# MD2_SE_Colour_Fix_-_PAL_rev2.net
KiCad netlist of a schematic drawn in EAGLE
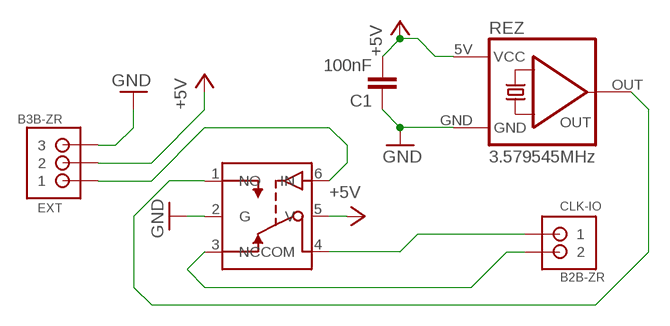
[diagram p0: schematic, sheet 1]

(export (version "E")
  (design (tool "Eeschema 10.0.6"))
  (components
    (comp (ref "C1")
      (value "100nF")
      (footprint "eagle-import:C0603K")
      (libsource (lib "eagle-import") (part "C-EUC0603K"))
    )
    (comp (ref "CLK-IO")
      (value "B2B-ZR")
      (footprint "eagle-import:B2B-ZR")
      (libsource (lib "eagle-import") (part "B2B-ZR"))
    )
    (comp (ref "EXT")
      (value "B3B-ZR")
      (footprint "eagle-import:B3B-ZR")
      (libsource (lib "eagle-import") (part "B3B-ZR"))
    )
    (comp (ref "REZ")
      (value "3.579545MHz")
      (footprint "eagle-import:DIL14S")
      (libsource (lib "eagle-import") (part "QG5860"))
    )
    (comp (ref "SWITCH")
      (value "TS5A3157EUT-T")
      (footprint "eagle-import:SOT23-6")
      (libsource (lib "eagle-import") (part "TS5A3157EUT-T"))
    )
  )
  (nets
    (net (code "1") (name "+5V") (class "Default")
      (node (ref "C1") (pin "2") (pinfunction "2_2") (pintype "passive"))
      (node (ref "EXT") (pin "2") (pinfunction "2_2") (pintype "bidirectional"))
      (node (ref "REZ") (pin "5V") (pinfunction "VCC_5V") (pintype "power_in"))
      (node (ref "SWITCH") (pin "5") (pinfunction "V_5") (pintype "power_in"))
    )
    (net (code "2") (name "GND") (class "Default")
      (node (ref "C1") (pin "1") (pinfunction "1_1") (pintype "passive"))
      (node (ref "EXT") (pin "3") (pinfunction "3_3") (pintype "bidirectional"))
      (node (ref "REZ") (pin "GND") (pinfunction "GND_GND") (pintype "power_in"))
      (node (ref "SWITCH") (pin "2") (pinfunction "G_2") (pintype "bidirectional"))
    )
    (net (code "3") (name "Net-(SWITCH-COM)") (class "Default")
      (node (ref "CLK-IO") (pin "1") (pinfunction "1_1") (pintype "bidirectional"))
      (node (ref "SWITCH") (pin "4") (pinfunction "COM_4") (pintype "bidirectional"))
    )
    (net (code "4") (name "Net-(SWITCH-IN)") (class "Default")
      (node (ref "EXT") (pin "1") (pinfunction "1_1") (pintype "bidirectional"))
      (node (ref "SWITCH") (pin "6") (pinfunction "IN_6") (pintype "input"))
    )
    (net (code "5") (name "Net-(SWITCH-NC)") (class "Default")
      (node (ref "CLK-IO") (pin "2") (pinfunction "2_2") (pintype "bidirectional"))
      (node (ref "SWITCH") (pin "3") (pinfunction "NC_3") (pintype "bidirectional"))
    )
    (net (code "6") (name "Net-(SWITCH-NO)") (class "Default")
      (node (ref "REZ") (pin "OUT") (pinfunction "OUT_OUT") (pintype "output"))
      (node (ref "SWITCH") (pin "1") (pinfunction "NO_1") (pintype "bidirectional"))
    )
  )
)
